# usb-to-serial.net
KiCad netlist of a schematic drawn in EAGLE
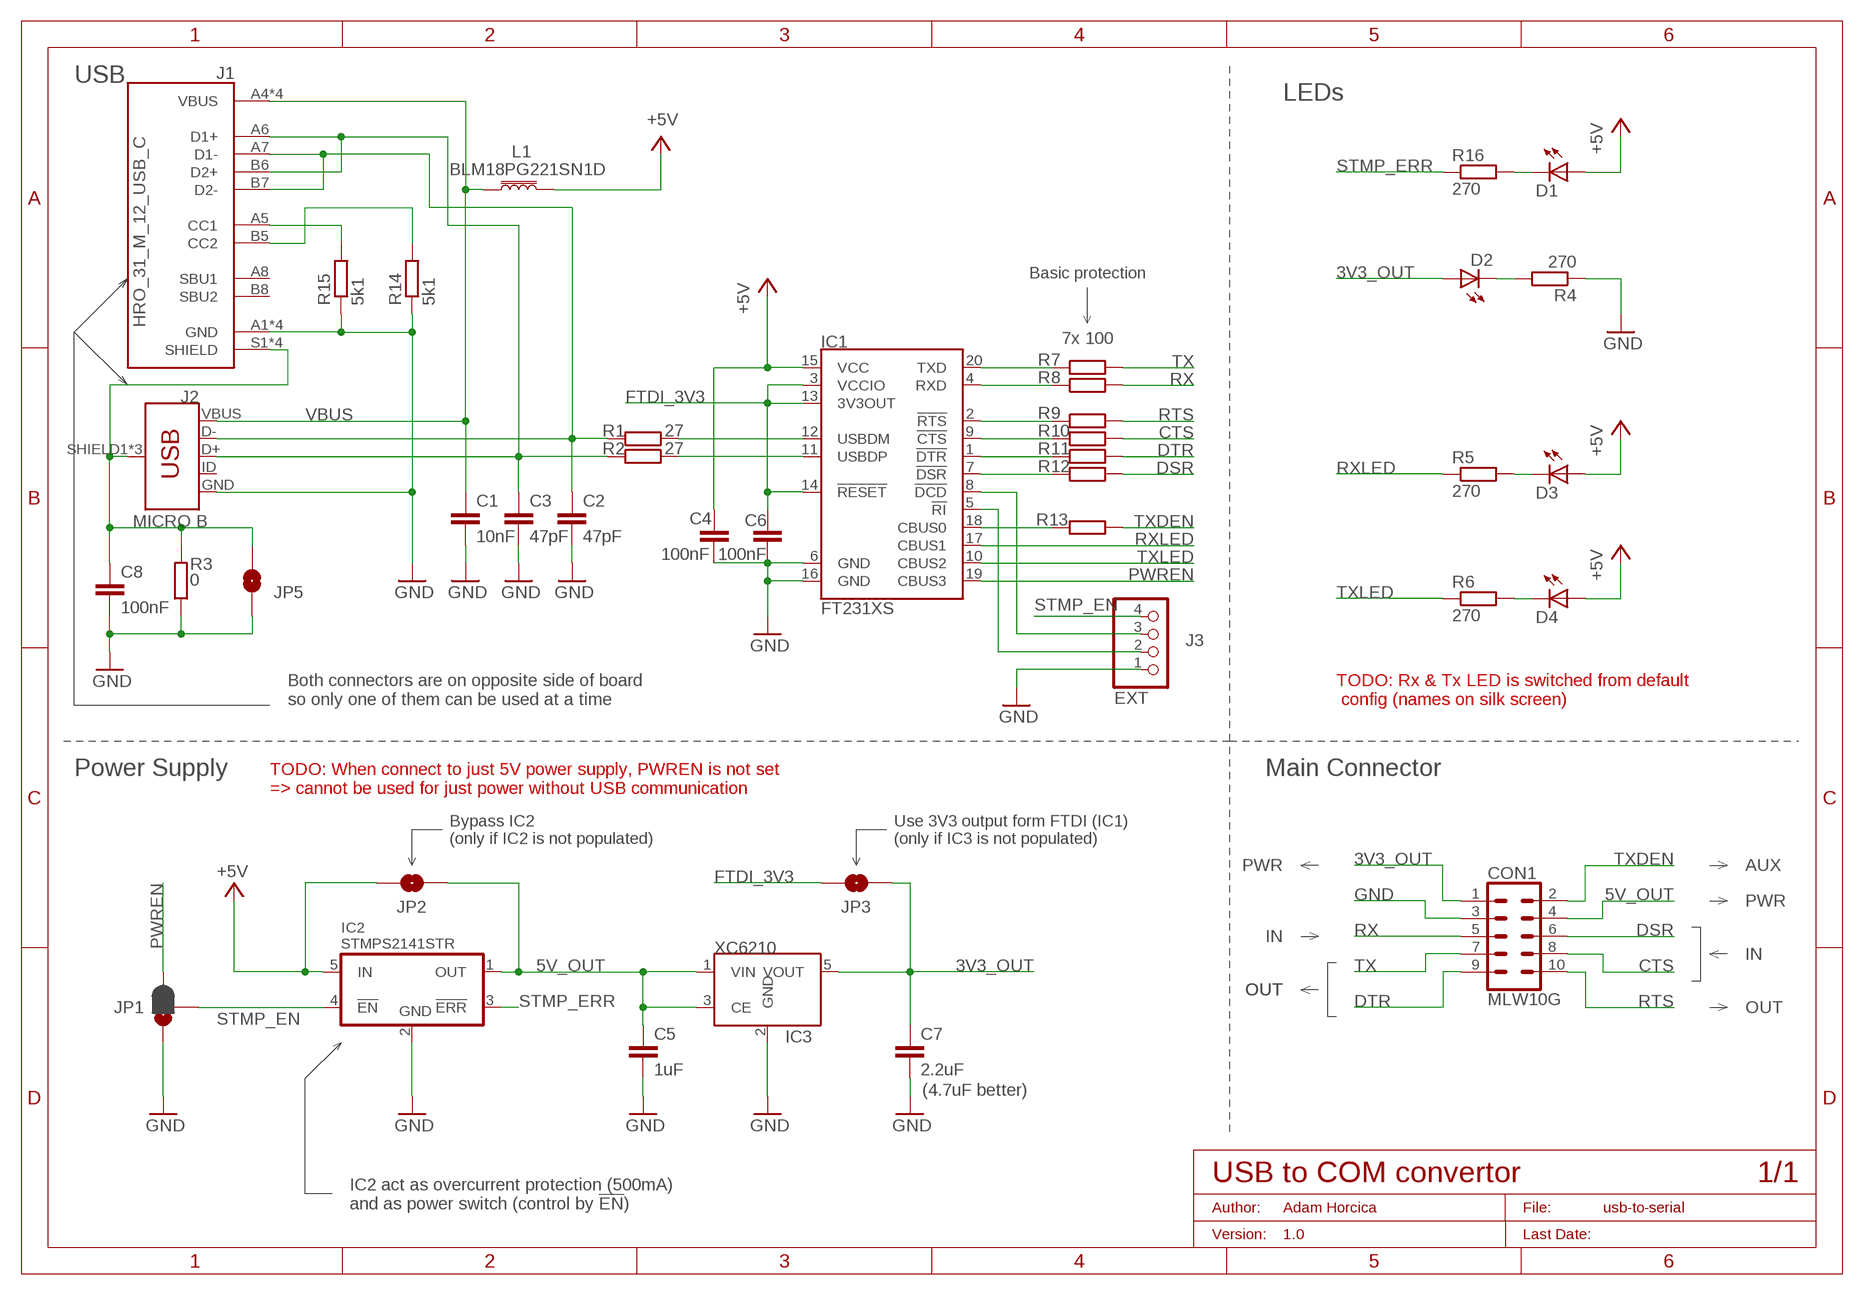
[diagram p0: schematic, sheet 1]

(export (version "E")
  (design (tool "Eeschema 10.0.6"))
  (components
    (comp (ref "C1")
      (value "10nF")
      (footprint "eagle-import:C0603")
      (libsource (lib "eagle-import") (part "C-EUC0603"))
    )
    (comp (ref "C2")
      (value "47pF")
      (footprint "eagle-import:C0603")
      (libsource (lib "eagle-import") (part "C-EUC0603"))
    )
    (comp (ref "C3")
      (value "47pF")
      (footprint "eagle-import:C0603")
      (libsource (lib "eagle-import") (part "C-EUC0603"))
    )
    (comp (ref "C4")
      (value "100nF")
      (footprint "eagle-import:C0603")
      (libsource (lib "eagle-import") (part "C-EUC0603"))
    )
    (comp (ref "C5")
      (value "1uF")
      (footprint "eagle-import:C0603")
      (libsource (lib "eagle-import") (part "C-EUC0603"))
    )
    (comp (ref "C6")
      (value "100nF")
      (footprint "eagle-import:C0603")
      (libsource (lib "eagle-import") (part "C-EUC0603"))
    )
    (comp (ref "C7")
      (value "2.2uF")
      (footprint "eagle-import:C0603")
      (libsource (lib "eagle-import") (part "C-EUC0603"))
    )
    (comp (ref "C8")
      (value "100nF")
      (footprint "eagle-import:C0603")
      (libsource (lib "eagle-import") (part "C-EUC0603"))
    )
    (comp (ref "CON1")
      (value "MLW10G")
      (footprint "eagle-import:MLW10G")
      (libsource (lib "eagle-import") (part "MLW10G"))
    )
    (comp (ref "D1")
      (value "LEDCHIP-LED0805")
      (footprint "eagle-import:CHIP-LED0805")
      (libsource (lib "eagle-import") (part "LEDCHIP-LED0805"))
    )
    (comp (ref "D2")
      (value "LEDCHIP-LED0805")
      (footprint "eagle-import:CHIP-LED0805")
      (libsource (lib "eagle-import") (part "LEDCHIP-LED0805"))
    )
    (comp (ref "D3")
      (value "LEDCHIP-LED0805")
      (footprint "eagle-import:CHIP-LED0805")
      (libsource (lib "eagle-import") (part "LEDCHIP-LED0805"))
    )
    (comp (ref "D4")
      (value "LEDCHIP-LED0805")
      (footprint "eagle-import:CHIP-LED0805")
      (libsource (lib "eagle-import") (part "LEDCHIP-LED0805"))
    )
    (comp (ref "EXT")
      (value "J3")
      (footprint "eagle-import:1X04")
      (libsource (lib "eagle-import") (part "PINHD-1X4"))
    )
    (comp (ref "IC1")
      (value "FT231XS")
      (footprint "eagle-import:SSOP20_L")
      (libsource (lib "eagle-import") (part "FT231XS"))
    )
    (comp (ref "IC2")
      (value "STMPS2141STR")
      (footprint "eagle-import:SOT23-5")
      (libsource (lib "eagle-import") (part "STMPS2141STR"))
    )
    (comp (ref "IC3")
      (value "XC6210")
      (footprint "eagle-import:SOT-23-5")
      (libsource (lib "eagle-import") (part "XC6210"))
    )
    (comp (ref "J1")
      (value "HRO_31_M_12_USB_C")
      (footprint "eagle-import:HRO_31_M_12_USB_C")
      (libsource (lib "eagle-import") (part "HRO_31_M_12_USB_C"))
    )
    (comp (ref "J2")
      (value "MICRO B")
      (footprint "eagle-import:USB-B-MICRO-SMD")
      (libsource (lib "eagle-import") (part "USB_MICRO-B_FEMALE-SMT"))
    )
    (comp (ref "JP1")
      (value "JUMPER-SMT_3_1-NC_PASTE_NO-SILK")
      (footprint "eagle-import:SMT-JUMPER_3_1-NC_PASTE_NO-SILK")
      (libsource (lib "eagle-import") (part "JUMPER-SMT_3_1-NC_PASTE_NO-SILK"))
    )
    (comp (ref "JP2")
      (value "JUMPER-SMT_2_NO_NO-SILK")
      (footprint "eagle-import:SMT-JUMPER_2_NO_NO-SILK")
      (libsource (lib "eagle-import") (part "JUMPER-SMT_2_NO_NO-SILK"))
    )
    (comp (ref "JP3")
      (value "JUMPER-SMT_2_NO_NO-SILK")
      (footprint "eagle-import:SMT-JUMPER_2_NO_NO-SILK")
      (libsource (lib "eagle-import") (part "JUMPER-SMT_2_NO_NO-SILK"))
    )
    (comp (ref "JP5")
      (value "JUMPER-SMT_2_NO_NO-SILK")
      (footprint "eagle-import:SMT-JUMPER_2_NO_NO-SILK")
      (libsource (lib "eagle-import") (part "JUMPER-SMT_2_NO_NO-SILK"))
    )
    (comp (ref "L1")
      (value "BLM18PG221SN1D")
      (footprint "eagle-import:0603")
      (libsource (lib "eagle-import") (part "FERRITE_BEAD-0603"))
    )
    (comp (ref "R1")
      (value "27")
      (footprint "eagle-import:R0603")
      (libsource (lib "eagle-import") (part "R-EU_R0603"))
    )
    (comp (ref "R2")
      (value "27")
      (footprint "eagle-import:R0603")
      (libsource (lib "eagle-import") (part "R-EU_R0603"))
    )
    (comp (ref "R3")
      (value "0")
      (footprint "eagle-import:R0603")
      (libsource (lib "eagle-import") (part "R-EU_R0603"))
    )
    (comp (ref "R4")
      (value "270")
      (footprint "eagle-import:R0603")
      (libsource (lib "eagle-import") (part "R-EU_R0603"))
    )
    (comp (ref "R5")
      (value "270")
      (footprint "eagle-import:R0603")
      (libsource (lib "eagle-import") (part "R-EU_R0603"))
    )
    (comp (ref "R6")
      (value "270")
      (footprint "eagle-import:R0603")
      (libsource (lib "eagle-import") (part "R-EU_R0603"))
    )
    (comp (ref "R7")
      (value "100")
      (footprint "eagle-import:R0603")
      (libsource (lib "eagle-import") (part "R-EU_R0603"))
    )
    (comp (ref "R8")
      (value "100")
      (footprint "eagle-import:R0603")
      (libsource (lib "eagle-import") (part "R-EU_R0603"))
    )
    (comp (ref "R9")
      (value "100")
      (footprint "eagle-import:R0603")
      (libsource (lib "eagle-import") (part "R-EU_R0603"))
    )
    (comp (ref "R10")
      (value "100")
      (footprint "eagle-import:R0603")
      (libsource (lib "eagle-import") (part "R-EU_R0603"))
    )
    (comp (ref "R11")
      (value "100")
      (footprint "eagle-import:R0603")
      (libsource (lib "eagle-import") (part "R-EU_R0603"))
    )
    (comp (ref "R12")
      (value "100")
      (footprint "eagle-import:R0603")
      (libsource (lib "eagle-import") (part "R-EU_R0603"))
    )
    (comp (ref "R13")
      (value "100")
      (footprint "eagle-import:R0603")
      (libsource (lib "eagle-import") (part "R-EU_R0603"))
    )
    (comp (ref "R14")
      (value "5k1")
      (footprint "eagle-import:R0603")
      (libsource (lib "eagle-import") (part "R-EU_R0603"))
    )
    (comp (ref "R15")
      (value "5k1")
      (footprint "eagle-import:R0603")
      (libsource (lib "eagle-import") (part "R-EU_R0603"))
    )
    (comp (ref "R16")
      (value "270")
      (footprint "eagle-import:R0603")
      (libsource (lib "eagle-import") (part "R-EU_R0603"))
    )
  )
  (nets
    (net (code "1") (name "+5V") (class "Default")
      (node (ref "C4") (pin "1") (pinfunction "1_1") (pintype "passive"))
      (node (ref "D1") (pin "A") (pinfunction "A_A") (pintype "passive"))
      (node (ref "D3") (pin "A") (pinfunction "A_A") (pintype "passive"))
      (node (ref "D4") (pin "A") (pinfunction "A_A") (pintype "passive"))
      (node (ref "IC1") (pin "15") (pinfunction "VCC_15") (pintype "bidirectional"))
      (node (ref "IC2") (pin "5") (pinfunction "IN_5") (pintype "input"))
      (node (ref "JP2") (pin "1") (pinfunction "1_1") (pintype "passive"))
      (node (ref "L1") (pin "1") (pinfunction "1_1") (pintype "passive"))
    )
    (net (code "2") (name "/3V3_OUT") (class "Default")
      (node (ref "C7") (pin "1") (pinfunction "1_1") (pintype "passive"))
      (node (ref "CON1") (pin "1") (pinfunction "1_1") (pintype "passive"))
      (node (ref "D2") (pin "A") (pinfunction "A_A") (pintype "passive"))
      (node (ref "IC3") (pin "5") (pinfunction "VOUT_5") (pintype "power_in"))
      (node (ref "JP3") (pin "2") (pinfunction "2_2") (pintype "passive"))
    )
    (net (code "3") (name "/5V_OUT") (class "Default")
      (node (ref "C5") (pin "1") (pinfunction "1_1") (pintype "passive"))
      (node (ref "CON1") (pin "4") (pinfunction "4_4") (pintype "passive"))
      (node (ref "IC2") (pin "1") (pinfunction "OUT_1") (pintype "passive"))
      (node (ref "IC3") (pin "1") (pinfunction "VIN_1") (pintype "power_in"))
      (node (ref "IC3") (pin "3") (pinfunction "CE_3") (pintype "power_in"))
      (node (ref "JP2") (pin "2") (pinfunction "2_2") (pintype "passive"))
    )
    (net (code "4") (name "/CTS") (class "Default")
      (node (ref "CON1") (pin "8") (pinfunction "8_8") (pintype "passive"))
      (node (ref "R10") (pin "2") (pinfunction "2_2") (pintype "passive"))
    )
    (net (code "5") (name "/DSR") (class "Default")
      (node (ref "CON1") (pin "6") (pinfunction "6_6") (pintype "passive"))
      (node (ref "R12") (pin "2") (pinfunction "2_2") (pintype "passive"))
    )
    (net (code "6") (name "/DTR") (class "Default")
      (node (ref "CON1") (pin "9") (pinfunction "9_9") (pintype "passive"))
      (node (ref "R11") (pin "2") (pinfunction "2_2") (pintype "passive"))
    )
    (net (code "7") (name "/FTDI_3V3") (class "Default")
      (node (ref "C6") (pin "1") (pinfunction "1_1") (pintype "passive"))
      (node (ref "IC1") (pin "13") (pinfunction "3V3OUT_13") (pintype "bidirectional"))
      (node (ref "IC1") (pin "14") (pinfunction "~{RESET}_14") (pintype "bidirectional"))
      (node (ref "IC1") (pin "3") (pinfunction "VCCIO_3") (pintype "bidirectional"))
      (node (ref "JP3") (pin "1") (pinfunction "1_1") (pintype "passive"))
    )
    (net (code "8") (name "/PWREN") (class "Default")
      (node (ref "IC1") (pin "19") (pinfunction "CBUS3_19") (pintype "bidirectional"))
      (node (ref "JP1") (pin "3") (pinfunction "3_3") (pintype "passive"))
    )
    (net (code "9") (name "/RTS") (class "Default")
      (node (ref "CON1") (pin "10") (pinfunction "10_10") (pintype "passive"))
      (node (ref "R9") (pin "2") (pinfunction "2_2") (pintype "passive"))
    )
    (net (code "10") (name "/RX") (class "Default")
      (node (ref "CON1") (pin "5") (pinfunction "5_5") (pintype "passive"))
      (node (ref "R8") (pin "2") (pinfunction "2_2") (pintype "passive"))
    )
    (net (code "11") (name "/RXLED") (class "Default")
      (node (ref "IC1") (pin "17") (pinfunction "CBUS1_17") (pintype "bidirectional"))
      (node (ref "R5") (pin "1") (pinfunction "1_1") (pintype "passive"))
    )
    (net (code "12") (name "/STMP_EN") (class "Default")
      (node (ref "EXT") (pin "4") (pinfunction "4_4") (pintype "passive"))
      (node (ref "IC2") (pin "4") (pinfunction "~{EN}_4") (pintype "passive"))
      (node (ref "JP1") (pin "2") (pinfunction "2_2") (pintype "passive"))
    )
    (net (code "13") (name "/STMP_ERR") (class "Default")
      (node (ref "IC2") (pin "3") (pinfunction "~{ERR}_3") (pintype "output"))
      (node (ref "R16") (pin "1") (pinfunction "1_1") (pintype "passive"))
    )
    (net (code "14") (name "/TX") (class "Default")
      (node (ref "CON1") (pin "7") (pinfunction "7_7") (pintype "passive"))
      (node (ref "R7") (pin "2") (pinfunction "2_2") (pintype "passive"))
    )
    (net (code "15") (name "/TXDEN") (class "Default")
      (node (ref "CON1") (pin "2") (pinfunction "2_2") (pintype "passive"))
      (node (ref "R13") (pin "2") (pinfunction "2_2") (pintype "passive"))
    )
    (net (code "16") (name "/TXLED") (class "Default")
      (node (ref "IC1") (pin "10") (pinfunction "CBUS2_10") (pintype "bidirectional"))
      (node (ref "R6") (pin "1") (pinfunction "1_1") (pintype "passive"))
    )
    (net (code "17") (name "/VBUS") (class "Default")
      (node (ref "C1") (pin "1") (pinfunction "1_1") (pintype "passive"))
      (node (ref "J1") (pin "A4") (pinfunction "VBUS_A4") (pintype "passive"))
      (node (ref "J1") (pin "A9") (pinfunction "VBUS_A9") (pintype "passive"))
      (node (ref "J1") (pin "B4") (pinfunction "VBUS_B4") (pintype "passive"))
      (node (ref "J1") (pin "B9") (pinfunction "VBUS_B9") (pintype "passive"))
      (node (ref "J2") (pin "VBUS") (pinfunction "VBUS_VBUS") (pintype "power_in"))
      (node (ref "L1") (pin "2") (pinfunction "2_2") (pintype "passive"))
    )
    (net (code "18") (name "GND") (class "Default")
      (node (ref "C1") (pin "2") (pinfunction "2_2") (pintype "passive"))
      (node (ref "C2") (pin "2") (pinfunction "2_2") (pintype "passive"))
      (node (ref "C3") (pin "2") (pinfunction "2_2") (pintype "passive"))
      (node (ref "C4") (pin "2") (pinfunction "2_2") (pintype "passive"))
      (node (ref "C5") (pin "2") (pinfunction "2_2") (pintype "passive"))
      (node (ref "C6") (pin "2") (pinfunction "2_2") (pintype "passive"))
      (node (ref "C7") (pin "2") (pinfunction "2_2") (pintype "passive"))
      (node (ref "C8") (pin "2") (pinfunction "2_2") (pintype "passive"))
      (node (ref "CON1") (pin "3") (pinfunction "3_3") (pintype "passive"))
      (node (ref "EXT") (pin "1") (pinfunction "1_1") (pintype "passive"))
      (node (ref "IC1") (pin "16") (pinfunction "GND_16") (pintype "bidirectional"))
      (node (ref "IC1") (pin "6") (pinfunction "GND_6") (pintype "bidirectional"))
      (node (ref "IC2") (pin "2") (pinfunction "GND_2") (pintype "power_in"))
      (node (ref "IC3") (pin "2") (pinfunction "GND_2") (pintype "power_in"))
      (node (ref "J1") (pin "A1") (pinfunction "GND_A1") (pintype "passive"))
      (node (ref "J1") (pin "A12") (pinfunction "GND_A12") (pintype "passive"))
      (node (ref "J1") (pin "B1") (pinfunction "GND_B1") (pintype "passive"))
      (node (ref "J1") (pin "B12") (pinfunction "GND_B12") (pintype "passive"))
      (node (ref "J2") (pin "GND") (pinfunction "GND_GND") (pintype "power_in"))
      (node (ref "JP1") (pin "1") (pinfunction "1_1") (pintype "passive"))
      (node (ref "JP5") (pin "1") (pinfunction "1_1") (pintype "passive"))
      (node (ref "R14") (pin "1") (pinfunction "1_1") (pintype "passive"))
      (node (ref "R15") (pin "1") (pinfunction "1_1") (pintype "passive"))
      (node (ref "R3") (pin "1") (pinfunction "1_1") (pintype "passive"))
      (node (ref "R4") (pin "1") (pinfunction "1_1") (pintype "passive"))
    )
    (net (code "19") (name "Net-(C8-Pad1)") (class "Default")
      (node (ref "C8") (pin "1") (pinfunction "1_1") (pintype "passive"))
      (node (ref "J1") (pin "S1") (pinfunction "SHIELD_S1") (pintype "passive"))
      (node (ref "J1") (pin "S2") (pinfunction "SHIELD_S2") (pintype "passive"))
      (node (ref "J1") (pin "S3") (pinfunction "SHIELD_S3") (pintype "passive"))
      (node (ref "J1") (pin "S4") (pinfunction "SHIELD_S4") (pintype "passive"))
      (node (ref "J2") (pin "SHIELD1") (pinfunction "SHIELD_SHIELD1") (pintype "bidirectional"))
      (node (ref "J2") (pin "SHIELD2") (pinfunction "SHIELD_SHIELD2") (pintype "bidirectional"))
      (node (ref "J2") (pin "SHIELD3") (pinfunction "SHIELD_SHIELD3") (pintype "bidirectional"))
      (node (ref "JP5") (pin "2") (pinfunction "2_2") (pintype "passive"))
      (node (ref "R3") (pin "2") (pinfunction "2_2") (pintype "passive"))
    )
    (net (code "20") (name "Net-(D1-PadC)") (class "Default")
      (node (ref "D1") (pin "C") (pinfunction "C_C") (pintype "passive"))
      (node (ref "R16") (pin "2") (pinfunction "2_2") (pintype "passive"))
    )
    (net (code "21") (name "Net-(D2-PadC)") (class "Default")
      (node (ref "D2") (pin "C") (pinfunction "C_C") (pintype "passive"))
      (node (ref "R4") (pin "2") (pinfunction "2_2") (pintype "passive"))
    )
    (net (code "22") (name "Net-(D3-PadC)") (class "Default")
      (node (ref "D3") (pin "C") (pinfunction "C_C") (pintype "passive"))
      (node (ref "R5") (pin "2") (pinfunction "2_2") (pintype "passive"))
    )
    (net (code "23") (name "Net-(D4-PadC)") (class "Default")
      (node (ref "D4") (pin "C") (pinfunction "C_C") (pintype "passive"))
      (node (ref "R6") (pin "2") (pinfunction "2_2") (pintype "passive"))
    )
    (net (code "24") (name "Net-(IC1-CBUS0)") (class "Default")
      (node (ref "IC1") (pin "18") (pinfunction "CBUS0_18") (pintype "bidirectional"))
      (node (ref "R13") (pin "1") (pinfunction "1_1") (pintype "passive"))
    )
    (net (code "25") (name "Net-(IC1-RXD)") (class "Default")
      (node (ref "IC1") (pin "4") (pinfunction "RXD_4") (pintype "bidirectional"))
      (node (ref "R8") (pin "1") (pinfunction "1_1") (pintype "passive"))
    )
    (net (code "26") (name "Net-(IC1-TXD)") (class "Default")
      (node (ref "IC1") (pin "20") (pinfunction "TXD_20") (pintype "bidirectional"))
      (node (ref "R7") (pin "1") (pinfunction "1_1") (pintype "passive"))
    )
    (net (code "27") (name "Net-(IC1-USBDM)") (class "Default")
      (node (ref "IC1") (pin "12") (pinfunction "USBDM_12") (pintype "bidirectional"))
      (node (ref "R1") (pin "2") (pinfunction "2_2") (pintype "passive"))
    )
    (net (code "28") (name "Net-(IC1-USBDP)") (class "Default")
      (node (ref "IC1") (pin "11") (pinfunction "USBDP_11") (pintype "bidirectional"))
      (node (ref "R2") (pin "2") (pinfunction "2_2") (pintype "passive"))
    )
    (net (code "29") (name "Net-(IC1-~{CTS})") (class "Default")
      (node (ref "IC1") (pin "9") (pinfunction "~{CTS}_9") (pintype "bidirectional"))
      (node (ref "R10") (pin "1") (pinfunction "1_1") (pintype "passive"))
    )
    (net (code "30") (name "Net-(IC1-~{DCD})") (class "Default")
      (node (ref "EXT") (pin "3") (pinfunction "3_3") (pintype "passive"))
      (node (ref "IC1") (pin "8") (pinfunction "~{DCD}_8") (pintype "bidirectional"))
    )
    (net (code "31") (name "Net-(IC1-~{DSR})") (class "Default")
      (node (ref "IC1") (pin "7") (pinfunction "~{DSR}_7") (pintype "bidirectional"))
      (node (ref "R12") (pin "1") (pinfunction "1_1") (pintype "passive"))
    )
    (net (code "32") (name "Net-(IC1-~{DTR})") (class "Default")
      (node (ref "IC1") (pin "1") (pinfunction "~{DTR}_1") (pintype "bidirectional"))
      (node (ref "R11") (pin "1") (pinfunction "1_1") (pintype "passive"))
    )
    (net (code "33") (name "Net-(IC1-~{RI})") (class "Default")
      (node (ref "EXT") (pin "2") (pinfunction "2_2") (pintype "passive"))
      (node (ref "IC1") (pin "5") (pinfunction "~{RI}_5") (pintype "bidirectional"))
    )
    (net (code "34") (name "Net-(IC1-~{RTS})") (class "Default")
      (node (ref "IC1") (pin "2") (pinfunction "~{RTS}_2") (pintype "bidirectional"))
      (node (ref "R9") (pin "1") (pinfunction "1_1") (pintype "passive"))
    )
    (net (code "35") (name "Net-(J1-CC1)") (class "Default")
      (node (ref "J1") (pin "A5") (pinfunction "CC1_A5") (pintype "passive"))
      (node (ref "R15") (pin "2") (pinfunction "2_2") (pintype "passive"))
    )
    (net (code "36") (name "Net-(J1-CC2)") (class "Default")
      (node (ref "J1") (pin "B5") (pinfunction "CC2_B5") (pintype "passive"))
      (node (ref "R14") (pin "2") (pinfunction "2_2") (pintype "passive"))
    )
    (net (code "37") (name "Net-(J1-D1+)") (class "Default")
      (node (ref "C3") (pin "1") (pinfunction "1_1") (pintype "passive"))
      (node (ref "J1") (pin "A6") (pinfunction "D1+_A6") (pintype "passive"))
      (node (ref "J1") (pin "B6") (pinfunction "D2+_B6") (pintype "passive"))
      (node (ref "J2") (pin "D+") (pinfunction "D+_D+") (pintype "bidirectional"))
      (node (ref "R2") (pin "1") (pinfunction "1_1") (pintype "passive"))
    )
    (net (code "38") (name "Net-(J1-D1-)") (class "Default")
      (node (ref "C2") (pin "1") (pinfunction "1_1") (pintype "passive"))
      (node (ref "J1") (pin "A7") (pinfunction "D1-_A7") (pintype "passive"))
      (node (ref "J1") (pin "B7") (pinfunction "D2-_B7") (pintype "passive"))
      (node (ref "J2") (pin "D-") (pinfunction "D-_D-") (pintype "bidirectional"))
      (node (ref "R1") (pin "1") (pinfunction "1_1") (pintype "passive"))
    )
    (net (code "39") (name "unconnected-(J1-SBU1-PadA8)") (class "Default")
      (node (ref "J1") (pin "A8") (pinfunction "SBU1_A8") (pintype "passive"))
    )
    (net (code "40") (name "unconnected-(J1-SBU2-PadB8)") (class "Default")
      (node (ref "J1") (pin "B8") (pinfunction "SBU2_B8") (pintype "passive"))
    )
    (net (code "41") (name "unconnected-(J2-PadID)") (class "Default")
      (node (ref "J2") (pin "ID") (pinfunction "ID_ID") (pintype "bidirectional"))
    )
  )
)
